# LaserDiode_Driver.net
KiCad netlist of a schematic drawn in Altium Designer
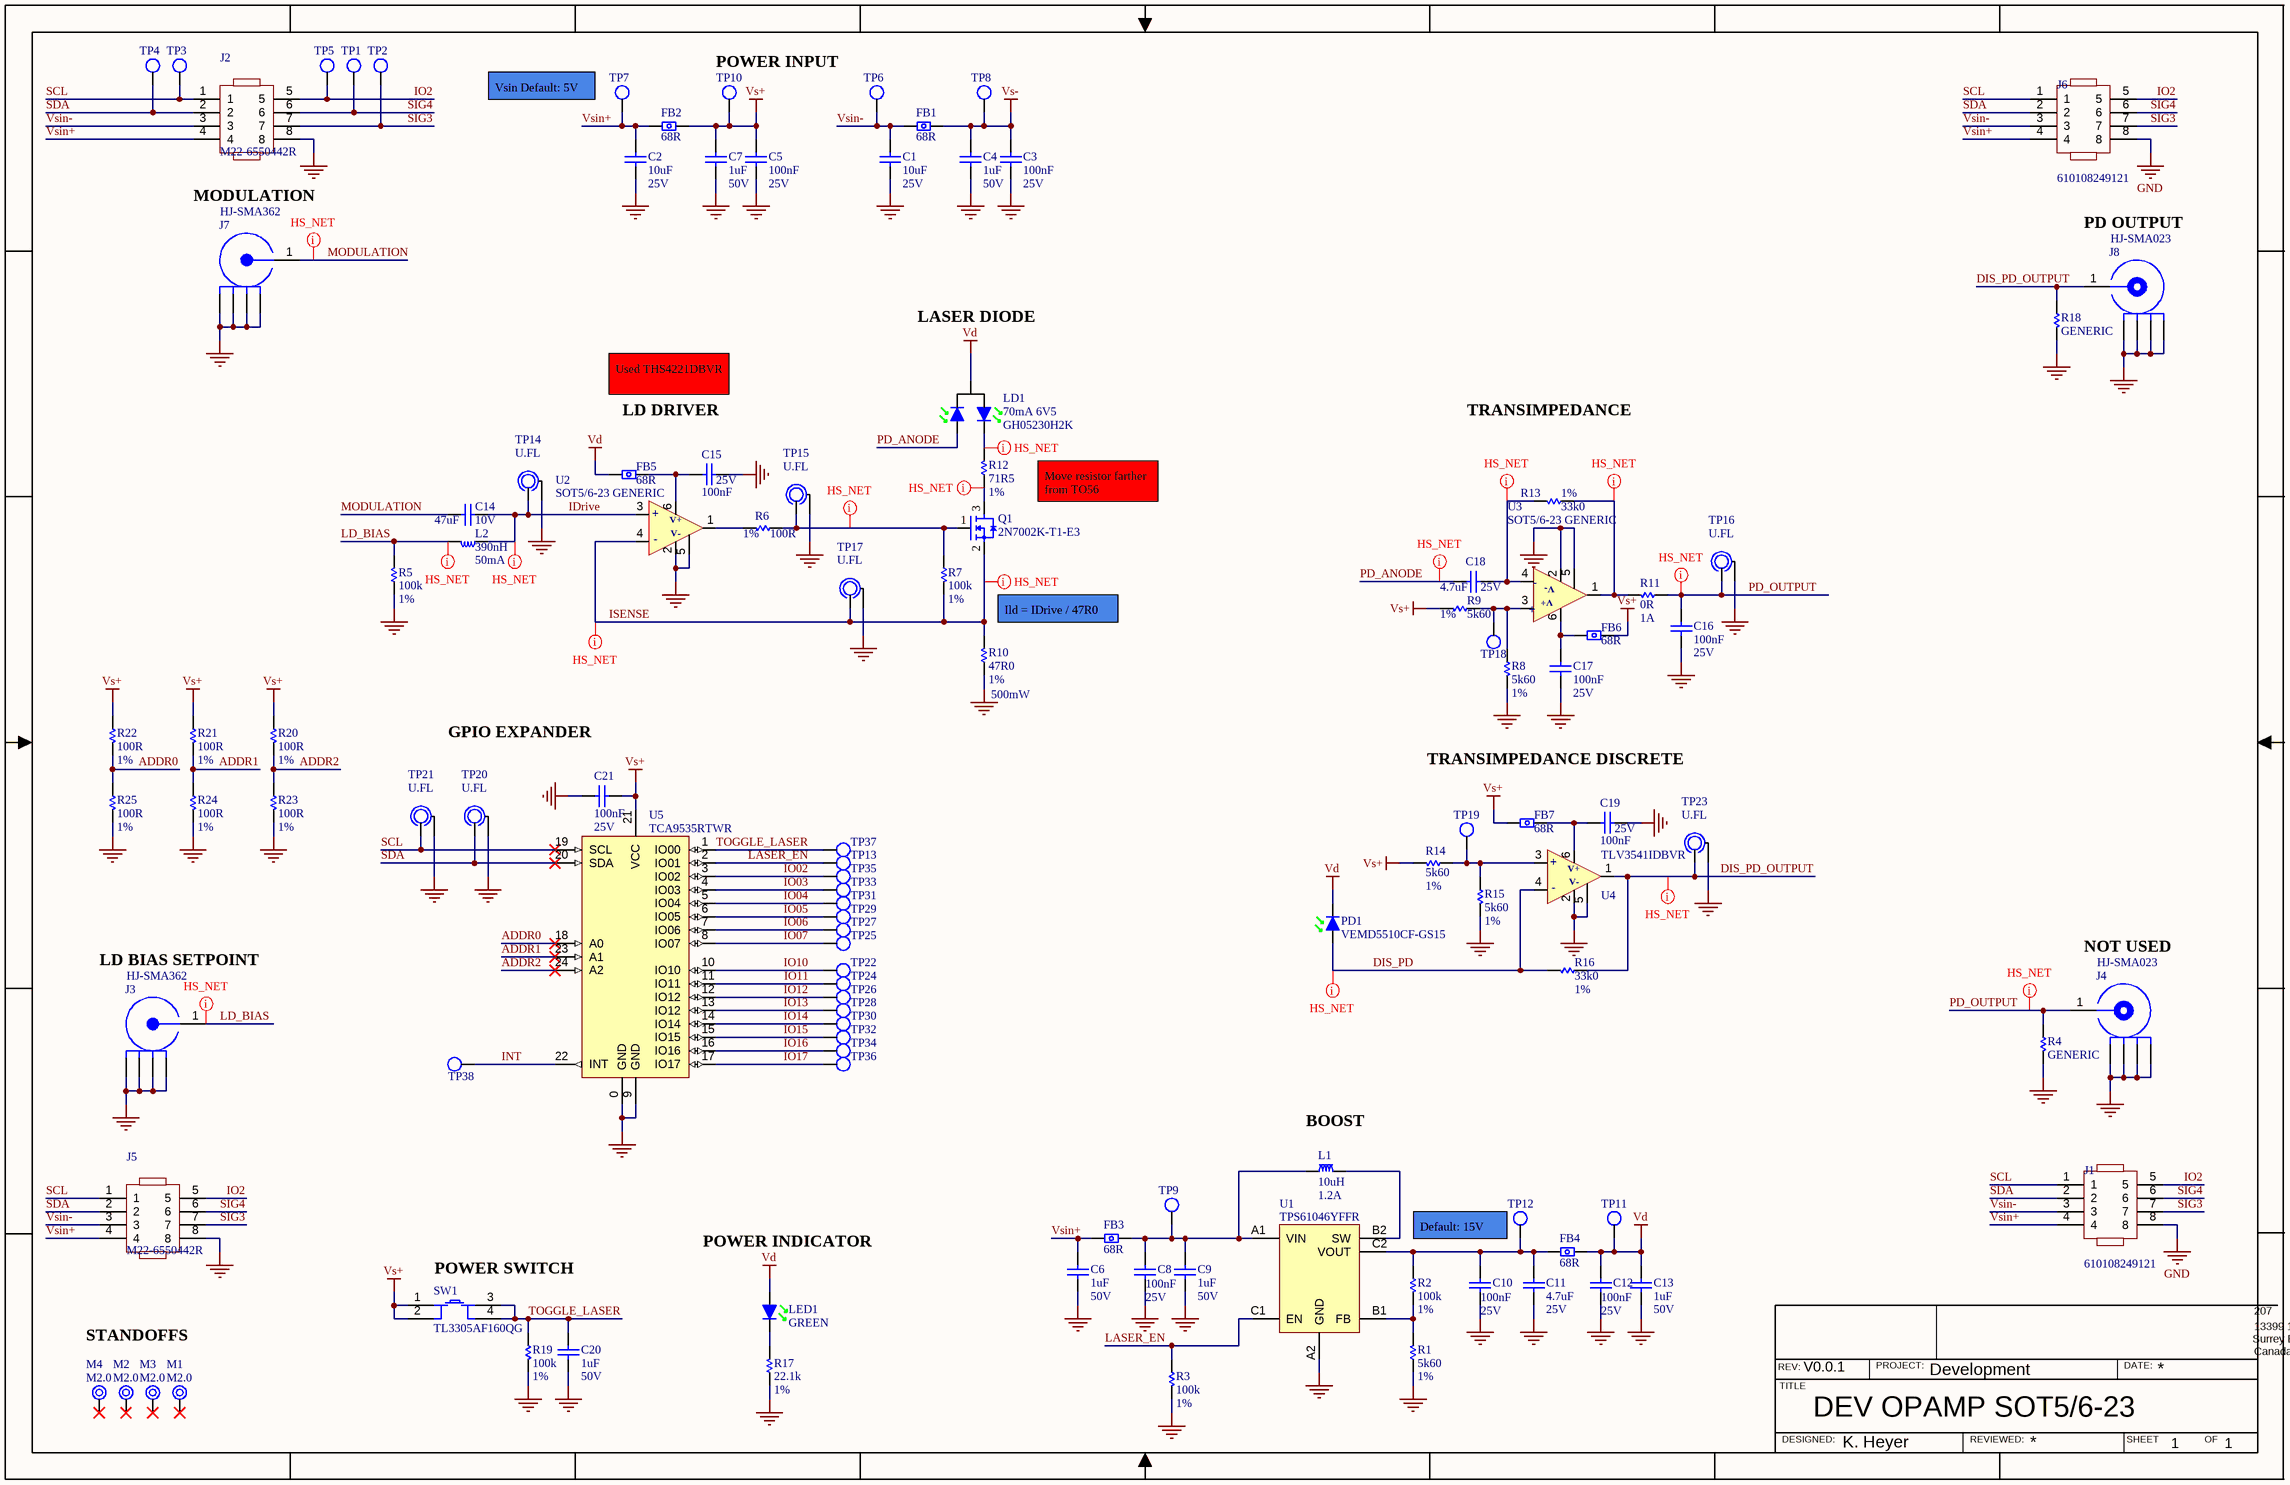
[diagram p0: LaserDiode_Driver.SchDoc]

(export (version "E")
  (design (tool "Eeschema 10.0.6"))
  (components
    (comp (ref "C1")
      (value "10uF")
      (footprint "c0805")
      (description "Cap Ceramic 10uF 25V X5R 10% SMD 0805 85°C Embossed T/R")
      (fields
        (field (name "MANUFACTURER") "Samsung")
        (field (name "MANUFACTURER PART NUMBER") "CL21A106KAYNNNE")
        (field (name "VOLTAGE RATING") "25V")
      )
      (libsource (lib "Symbols") (part "CAP CER 10uF 25V X5R 0805"))
    )
    (comp (ref "C2")
      (value "10uF")
      (footprint "c0805")
      (description "Cap Ceramic 10uF 25V X5R 10% SMD 0805 85°C Embossed T/R")
      (fields
        (field (name "MANUFACTURER") "Samsung")
        (field (name "MANUFACTURER PART NUMBER") "CL21A106KAYNNNE")
        (field (name "VOLTAGE RATING") "25V")
      )
      (libsource (lib "Symbols") (part "CAP CER 10uF 25V X5R 0805"))
    )
    (comp (ref "C3")
      (value "100nF")
      (footprint "C0402")
      (description "Cap Ceramic 0.1uF 25V X5R 10% Pad SMD 0402 85°C T/R / Multi Layer Ceramic Capacitor (MLCC)")
      (fields
        (field (name "MANUFACTURER") "Samsung")
        (field (name "MANUFACTURER PART NUMBER") "CL05A104KA5NNNC")
        (field (name "VOLTAGE RATING") "25V")
      )
      (libsource (lib "Symbols") (part "CAP CER 100nF 25V X5R 0402"))
    )
    (comp (ref "C4")
      (value "1uF")
      (footprint "c0603")
      (description "Multilayer Ceramic Capacitors (High dielectric type), 50V, 1 uF, ± 10 %, 0603, X5R, RoHS")
      (fields
        (field (name "MANUFACTURER") "Taiyo Yuden")
        (field (name "MANUFACTURER PART NUMBER") "UMK107BJ105KA-T")
        (field (name "VOLTAGE RATING") "50V")
      )
      (libsource (lib "Symbols") (part "CAP CER 1uF 50V X5R 0603"))
    )
    (comp (ref "C5")
      (value "100nF")
      (footprint "C0402")
      (description "Cap Ceramic 0.1uF 25V X5R 10% Pad SMD 0402 85°C T/R / Multi Layer Ceramic Capacitor (MLCC)")
      (fields
        (field (name "MANUFACTURER") "Samsung")
        (field (name "MANUFACTURER PART NUMBER") "CL05A104KA5NNNC")
        (field (name "VOLTAGE RATING") "25V")
      )
      (libsource (lib "Symbols") (part "CAP CER 100nF 25V X5R 0402"))
    )
    (comp (ref "C6")
      (value "1uF")
      (footprint "c0603")
      (description "Multilayer Ceramic Capacitors (High dielectric type), 50V, 1 uF, ± 10 %, 0603, X5R, RoHS")
      (fields
        (field (name "MANUFACTURER") "Taiyo Yuden")
        (field (name "MANUFACTURER PART NUMBER") "UMK107BJ105KA-T")
        (field (name "VOLTAGE RATING") "50V")
      )
      (libsource (lib "Symbols") (part "CAP CER 1uF 50V X5R 0603"))
    )
    (comp (ref "C7")
      (value "1uF")
      (footprint "c0603")
      (description "Multilayer Ceramic Capacitors (High dielectric type), 50V, 1 uF, ± 10 %, 0603, X5R, RoHS")
      (fields
        (field (name "MANUFACTURER") "Taiyo Yuden")
        (field (name "MANUFACTURER PART NUMBER") "UMK107BJ105KA-T")
        (field (name "VOLTAGE RATING") "50V")
      )
      (libsource (lib "Symbols") (part "CAP CER 1uF 50V X5R 0603"))
    )
    (comp (ref "C8")
      (value "100nF")
      (footprint "C0402")
      (description "Cap Ceramic 0.1uF 25V X5R 10% Pad SMD 0402 85°C T/R / Multi Layer Ceramic Capacitor (MLCC)")
      (fields
        (field (name "MANUFACTURER") "Samsung")
        (field (name "MANUFACTURER PART NUMBER") "CL05A104KA5NNNC")
        (field (name "VOLTAGE RATING") "25V")
      )
      (libsource (lib "Symbols") (part "CAP CER 100nF 25V X5R 0402"))
    )
    (comp (ref "C9")
      (value "1uF")
      (footprint "c0603")
      (description "Multilayer Ceramic Capacitors (High dielectric type), 50V, 1 uF, ± 10 %, 0603, X5R, RoHS")
      (fields
        (field (name "MANUFACTURER") "Taiyo Yuden")
        (field (name "MANUFACTURER PART NUMBER") "UMK107BJ105KA-T")
        (field (name "VOLTAGE RATING") "50V")
      )
      (libsource (lib "Symbols") (part "CAP CER 1uF 50V X5R 0603"))
    )
    (comp (ref "C10")
      (value "100nF")
      (footprint "C0402")
      (description "Cap Ceramic 0.1uF 25V X5R 10% Pad SMD 0402 85°C T/R / Multi Layer Ceramic Capacitor (MLCC)")
      (fields
        (field (name "MANUFACTURER") "Samsung")
        (field (name "MANUFACTURER PART NUMBER") "CL05A104KA5NNNC")
        (field (name "VOLTAGE RATING") "25V")
      )
      (libsource (lib "Symbols") (part "CAP CER 100nF 25V X5R 0402"))
    )
    (comp (ref "C11")
      (value "4.7uF")
      (footprint "c0805")
      (description "Cap Ceramic 4.7uF 25V X5R 10% SMD 0805 85C Embossed T/R")
      (fields
        (field (name "MANUFACTURER") "Samsung")
        (field (name "MANUFACTURER PART NUMBER") "CL21A475KAQNNNE")
        (field (name "VOLTAGE RATING") "25V")
      )
      (libsource (lib "Symbols") (part "CAP CER 4.7uF 25V X5R 0805"))
    )
    (comp (ref "C12")
      (value "100nF")
      (footprint "C0402")
      (description "Cap Ceramic 0.1uF 25V X5R 10% Pad SMD 0402 85°C T/R / Multi Layer Ceramic Capacitor (MLCC)")
      (fields
        (field (name "MANUFACTURER") "Samsung")
        (field (name "MANUFACTURER PART NUMBER") "CL05A104KA5NNNC")
        (field (name "VOLTAGE RATING") "25V")
      )
      (libsource (lib "Symbols") (part "CAP CER 100nF 25V X5R 0402"))
    )
    (comp (ref "C13")
      (value "1uF")
      (footprint "c0603")
      (description "Multilayer Ceramic Capacitors (High dielectric type), 50V, 1 uF, ± 10 %, 0603, X5R, RoHS")
      (fields
        (field (name "MANUFACTURER") "Taiyo Yuden")
        (field (name "MANUFACTURER PART NUMBER") "UMK107BJ105KA-T")
        (field (name "VOLTAGE RATING") "50V")
      )
      (libsource (lib "Symbols") (part "CAP CER 1uF 50V X5R 0603"))
    )
    (comp (ref "C14")
      (value "47uF")
      (footprint "C1210")
      (description "CAP CER 47UF 10V 20% X7R 1210")
      (fields
        (field (name "MANUFACTURER") "Murata")
        (field (name "MANUFACTURER PART NUMBER") "GRM32ER71A476ME15L")
        (field (name "VOLTAGE RATING") "10V")
      )
      (libsource (lib "Symbols") (part "CAP CER 47uF 10V X7R 1210"))
    )
    (comp (ref "C15")
      (value "100nF")
      (footprint "C0402")
      (description "Cap Ceramic 0.1uF 25V X5R 10% Pad SMD 0402 85°C T/R / Multi Layer Ceramic Capacitor (MLCC)")
      (fields
        (field (name "MANUFACTURER") "Samsung")
        (field (name "MANUFACTURER PART NUMBER") "CL05A104KA5NNNC")
        (field (name "VOLTAGE RATING") "25V")
      )
      (libsource (lib "Symbols") (part "CAP CER 100nF 25V X5R 0402"))
    )
    (comp (ref "C16")
      (value "100nF")
      (footprint "C0402")
      (description "Cap Ceramic 0.1uF 25V X5R 10% Pad SMD 0402 85°C T/R / Multi Layer Ceramic Capacitor (MLCC)")
      (fields
        (field (name "MANUFACTURER") "Samsung")
        (field (name "MANUFACTURER PART NUMBER") "CL05A104KA5NNNC")
        (field (name "VOLTAGE RATING") "25V")
      )
      (libsource (lib "Symbols") (part "CAP CER 100nF 25V X5R 0402"))
    )
    (comp (ref "C17")
      (value "100nF")
      (footprint "C0402")
      (description "Cap Ceramic 0.1uF 25V X5R 10% Pad SMD 0402 85°C T/R / Multi Layer Ceramic Capacitor (MLCC)")
      (fields
        (field (name "MANUFACTURER") "Samsung")
        (field (name "MANUFACTURER PART NUMBER") "CL05A104KA5NNNC")
        (field (name "VOLTAGE RATING") "25V")
      )
      (libsource (lib "Symbols") (part "CAP CER 100nF 25V X5R 0402"))
    )
    (comp (ref "C18")
      (value "4.7uF")
      (footprint "c0805")
      (description "Cap Ceramic 4.7uF 25V X5R 10% SMD 0805 85C Embossed T/R")
      (fields
        (field (name "MANUFACTURER") "Samsung")
        (field (name "MANUFACTURER PART NUMBER") "CL21A475KAQNNNE")
        (field (name "VOLTAGE RATING") "25V")
      )
      (libsource (lib "Symbols") (part "CAP CER 4.7uF 25V X5R 0805"))
    )
    (comp (ref "C19")
      (value "100nF")
      (footprint "C0402")
      (description "Cap Ceramic 0.1uF 25V X5R 10% Pad SMD 0402 85°C T/R / Multi Layer Ceramic Capacitor (MLCC)")
      (fields
        (field (name "MANUFACTURER") "Samsung")
        (field (name "MANUFACTURER PART NUMBER") "CL05A104KA5NNNC")
        (field (name "VOLTAGE RATING") "25V")
      )
      (libsource (lib "Symbols") (part "CAP CER 100nF 25V X5R 0402"))
    )
    (comp (ref "C20")
      (value "1uF")
      (footprint "c0603")
      (description "Multilayer Ceramic Capacitors (High dielectric type), 50V, 1 uF, ± 10 %, 0603, X5R, RoHS")
      (fields
        (field (name "MANUFACTURER") "Taiyo Yuden")
        (field (name "MANUFACTURER PART NUMBER") "UMK107BJ105KA-T")
        (field (name "VOLTAGE RATING") "50V")
      )
      (libsource (lib "Symbols") (part "CAP CER 1uF 50V X5R 0603"))
    )
    (comp (ref "C21")
      (value "100nF")
      (footprint "C0402")
      (description "Cap Ceramic 0.1uF 25V X5R 10% Pad SMD 0402 85°C T/R / Multi Layer Ceramic Capacitor (MLCC)")
      (fields
        (field (name "MANUFACTURER") "Samsung")
        (field (name "MANUFACTURER PART NUMBER") "CL05A104KA5NNNC")
        (field (name "VOLTAGE RATING") "25V")
      )
      (libsource (lib "Symbols") (part "CAP CER 100nF 25V X5R 0402"))
    )
    (comp (ref "FB1")
      (value "68R")
      (footprint "FB0402")
      (description "Ferrite Beads Multi-Layer 68Ohm 25% 100MHz 400mA 310mOhm DCR 0402 T/R")
      (fields
        (field (name "MANUFACTURER") "Taiyo Yuden")
        (field (name "MANUFACTURER PART NUMBER") "BK1005LL680-T")
      )
      (libsource (lib "Symbols") (part "FB 68R 400mA 310mR 0402"))
    )
    (comp (ref "FB2")
      (value "68R")
      (footprint "FB0402")
      (description "Ferrite Beads Multi-Layer 68Ohm 25% 100MHz 400mA 310mOhm DCR 0402 T/R")
      (fields
        (field (name "MANUFACTURER") "Taiyo Yuden")
        (field (name "MANUFACTURER PART NUMBER") "BK1005LL680-T")
      )
      (libsource (lib "Symbols") (part "FB 68R 400mA 310mR 0402"))
    )
    (comp (ref "FB3")
      (value "68R")
      (footprint "FB0402")
      (description "Ferrite Beads Multi-Layer 68Ohm 25% 100MHz 400mA 310mOhm DCR 0402 T/R")
      (fields
        (field (name "MANUFACTURER") "Taiyo Yuden")
        (field (name "MANUFACTURER PART NUMBER") "BK1005LL680-T")
      )
      (libsource (lib "Symbols") (part "FB 68R 400mA 310mR 0402"))
    )
    (comp (ref "FB4")
      (value "68R")
      (footprint "FB0402")
      (description "Ferrite Beads Multi-Layer 68Ohm 25% 100MHz 400mA 310mOhm DCR 0402 T/R")
      (fields
        (field (name "MANUFACTURER") "Taiyo Yuden")
        (field (name "MANUFACTURER PART NUMBER") "BK1005LL680-T")
      )
      (libsource (lib "Symbols") (part "FB 68R 400mA 310mR 0402"))
    )
    (comp (ref "FB5")
      (value "68R")
      (footprint "FB0402")
      (description "Ferrite Beads Multi-Layer 68Ohm 25% 100MHz 400mA 310mOhm DCR 0402 T/R")
      (fields
        (field (name "MANUFACTURER") "Taiyo Yuden")
        (field (name "MANUFACTURER PART NUMBER") "BK1005LL680-T")
      )
      (libsource (lib "Symbols") (part "FB 68R 400mA 310mR 0402"))
    )
    (comp (ref "FB6")
      (value "68R")
      (footprint "FB0402")
      (description "Ferrite Beads Multi-Layer 68Ohm 25% 100MHz 400mA 310mOhm DCR 0402 T/R")
      (fields
        (field (name "MANUFACTURER") "Taiyo Yuden")
        (field (name "MANUFACTURER PART NUMBER") "BK1005LL680-T")
      )
      (libsource (lib "Symbols") (part "FB 68R 400mA 310mR 0402"))
    )
    (comp (ref "FB7")
      (value "68R")
      (footprint "FB0402")
      (description "Ferrite Beads Multi-Layer 68Ohm 25% 100MHz 400mA 310mOhm DCR 0402 T/R")
      (fields
        (field (name "MANUFACTURER") "Taiyo Yuden")
        (field (name "MANUFACTURER PART NUMBER") "BK1005LL680-T")
      )
      (libsource (lib "Symbols") (part "FB 68R 400mA 310mR 0402"))
    )
    (comp (ref "J1")
      (value "610108249121")
      (footprint "CONN HDR 08 MALE RA 2ROW - duplicate")
      (description "SMT Angled Pin Header WR-PHD, Pitch 2.54 mm, Dual Row, 8 pins")
      (fields (field (name "MANUFACTURER") "Wurth Electronics"))
      (libsource (lib "Symbols") (part "CONN HDR 08 MALE RA 2 ROW"))
    )
    (comp (ref "J2")
      (value "M22-6550442R")
      (footprint "CONN HDR 08 FEMALE RA 2ROW")
      (description "Conn Socket Strip RCP 8 POS 2mm Solder RA SMD T/R")
      (fields (field (name "MANUFACTURER") "Harwin"))
      (libsource (lib "Symbols") (part "CONN HDR 08 FEMALE RA 2 ROW"))
    )
    (comp (ref "J3")
      (value "HJ-SMA362")
      (footprint "SMA SMD PIN BRD EDGE")
      (libsource (lib "Symbols") (part "CON SMA PIN SMD BRD EDGE HJ-SMA362"))
    )
    (comp (ref "J4")
      (value "HJ-SMA023")
      (footprint "SMA SMD BORE BRD EDGE")
      (libsource (lib "Symbols") (part "CON SMA BORE SMD BRD EDGE HJ-SMA023"))
    )
    (comp (ref "J5")
      (value "M22-6550442R")
      (footprint "CONN HDR 08 FEMALE RA 2ROW")
      (description "Conn Socket Strip RCP 8 POS 2mm Solder RA SMD T/R")
      (fields (field (name "MANUFACTURER") "Harwin"))
      (libsource (lib "Symbols") (part "CONN HDR 08 FEMALE RA 2 ROW"))
    )
    (comp (ref "J6")
      (value "610108249121")
      (footprint "CONN HDR 08 MALE RA 2ROW - duplicate")
      (description "SMT Angled Pin Header WR-PHD, Pitch 2.54 mm, Dual Row, 8 pins")
      (fields (field (name "MANUFACTURER") "Wurth Electronics"))
      (libsource (lib "Symbols") (part "CONN HDR 08 MALE RA 2 ROW"))
    )
    (comp (ref "J7")
      (value "HJ-SMA362")
      (footprint "SMA SMD PIN BRD EDGE")
      (libsource (lib "Symbols") (part "CON SMA PIN SMD BRD EDGE HJ-SMA362"))
    )
    (comp (ref "J8")
      (value "HJ-SMA023")
      (footprint "SMA SMD BORE BRD EDGE")
      (libsource (lib "Symbols") (part "CON SMA BORE SMD BRD EDGE HJ-SMA023"))
    )
    (comp (ref "L1")
      (value "10uH")
      (footprint "INDP4040X27N")
      (description "Inductor Power Shielded Wirewound 10uH 20% 100KHz Ferrite 1.2A 0.18Ohm DCR 1515 T/R")
      (fields
        (field (name "MANUFACTURER") "Taiyo Yuden")
        (field (name "MANUFACTURER PART NUMBER") "NRS4018T100MDGJ")
        (field (name "CURRENT RATING") "1.2A")
      )
      (libsource (lib "Symbols") (part "IND 10uH 1.2A 180mR 4040 NRS4018T100MDGJ"))
    )
    (comp (ref "L2")
      (value "390nH")
      (footprint "L0402")
      (fields
        (field (name "MANUFACTURER") "TDK")
        (field (name "MANUFACTURER PART NUMBER") "MLG1005SR39JT000")
        (field (name "TOLERANCE") "5%")
        (field (name "CURRENT RATING") "50mA")
      )
      (libsource (lib "Symbols") (part "IND HF 390nH 50mA 8R 0402"))
    )
    (comp (ref "LD1")
      (value "70mA 6V5")
      (footprint "LD TO-56")
      (fields (field (name "MANUFACTURER") "Sharp") (field (name "MANUFACTURER PART NUMBER") "GH05230H2K"))
      (libsource (lib "Symbols") (part "LD TYPE A GREEN 30mW GH05230H2K"))
    )
    (comp (ref "LED1")
      (value "GREEN")
      (footprint "led0402 green")
      (description "LED GREEN CLEAR 0402 SMD")
      (fields
        (field (name "MANUFACTURER") "Kingbright")
        (field (name "MANUFACTURER PART NUMBER") "APHHS1005CGCK")
      )
      (libsource (lib "Symbols") (part "LED GREEN CLEAR 0402"))
    )
    (comp (ref "M1")
      (value "M2.0")
      (footprint "MECH M2.0 UNPLATED")
      (libsource (lib "Symbols") (part "MECH M2.0 UNPLATED"))
    )
    (comp (ref "M2")
      (value "M2.0")
      (footprint "MECH M2.0 UNPLATED")
      (libsource (lib "Symbols") (part "MECH M2.0 UNPLATED"))
    )
    (comp (ref "M3")
      (value "M2.0")
      (footprint "MECH M2.0 UNPLATED")
      (libsource (lib "Symbols") (part "MECH M2.0 UNPLATED"))
    )
    (comp (ref "M4")
      (value "M2.0")
      (footprint "MECH M2.0 UNPLATED")
      (libsource (lib "Symbols") (part "MECH M2.0 UNPLATED"))
    )
    (comp (ref "PD1")
      (value "VEMD5510CF-GS15")
      (footprint "PIN 4x5 4pin")
      (description "Photodiode PIN Chip 540nm 4-Pin SMD T/R")
      (libsource (lib "Symbols") (part "DIODE PHOTO 540nm 20V VEMD5510CF-GS15"))
    )
    (comp (ref "Q1")
      (value "2N7002K-T1-E3")
      (footprint "SOT 23-3")
      (description "Trans MOSFET N-CH 60V 0.3A 3-Pin SOT-23 T/R - Tape and Reel (Alt: 2N7002K-T1-E3)")
      (fields (field (name "MANUFACTURER") "Vishay Siliconix"))
      (libsource (lib "Symbols") (part "TRANS NMOS 60V SOT-23-3 2N7002K-T1-E3"))
    )
    (comp (ref "R1")
      (value "5k60")
      (footprint "R0402")
      (description "Res Thick Film 0402 5.6K Ohm 1% 0.063W(1/16W) ±100ppm/C Epoxy SMD T/R")
      (fields
        (field (name "MANUFACTURER") "Yageo")
        (field (name "MANUFACTURER PART NUMBER") "RC0402FR-075K6L")
        (field (name "TOLERANCE") "1%")
      )
      (libsource (lib "Symbols") (part "RES 5k60 1% 63mW 0402"))
    )
    (comp (ref "R2")
      (value "100k")
      (footprint "r0402")
      (description "Res Thick Film 0402 100K Ohm 1% 0.063W ±100ppm/°C Molded SMD Paper T/R")
      (fields
        (field (name "MANUFACTURER") "Stackpole Electronics")
        (field (name "MANUFACTURER PART NUMBER") "RMCF0402FT100K")
        (field (name "TOLERANCE") "1%")
      )
      (libsource (lib "Symbols") (part "RES 100k 1% 63mW 0402"))
    )
    (comp (ref "R3")
      (value "100k")
      (footprint "r0402")
      (description "Res Thick Film 0402 100K Ohm 1% 0.063W ±100ppm/°C Molded SMD Paper T/R")
      (fields
        (field (name "MANUFACTURER") "Stackpole Electronics")
        (field (name "MANUFACTURER PART NUMBER") "RMCF0402FT100K")
        (field (name "TOLERANCE") "1%")
      )
      (libsource (lib "Symbols") (part "RES 100k 1% 63mW 0402"))
    )
    (comp (ref "R4")
      (value "GENERIC")
      (footprint "R0402")
      (libsource (lib "Symbols") (part "RES GENERIC 0402"))
    )
    (comp (ref "R5")
      (value "100k")
      (footprint "r0402")
      (description "Res Thick Film 0402 100K Ohm 1% 0.063W ±100ppm/°C Molded SMD Paper T/R")
      (fields
        (field (name "MANUFACTURER") "Stackpole Electronics")
        (field (name "MANUFACTURER PART NUMBER") "RMCF0402FT100K")
        (field (name "TOLERANCE") "1%")
      )
      (libsource (lib "Symbols") (part "RES 100k 1% 63mW 0402"))
    )
    (comp (ref "R6")
      (value "100R")
      (footprint "R0402")
      (description "Res General Purpose Thick Film 0402 100 Ohm 1% 1/16W ±100ppm/°C Molded SMD Paper T/R")
      (fields
        (field (name "MANUFACTURER") "Yageo")
        (field (name "MANUFACTURER PART NUMBER") "RC0402FR-07100RL")
        (field (name "TOLERANCE") "1%")
      )
      (libsource (lib "Symbols") (part "RES 100R 63mW 1% 0402"))
    )
    (comp (ref "R7")
      (value "100k")
      (footprint "r0402")
      (description "Res Thick Film 0402 100K Ohm 1% 0.063W ±100ppm/°C Molded SMD Paper T/R")
      (fields
        (field (name "MANUFACTURER") "Stackpole Electronics")
        (field (name "MANUFACTURER PART NUMBER") "RMCF0402FT100K")
        (field (name "TOLERANCE") "1%")
      )
      (libsource (lib "Symbols") (part "RES 100k 1% 63mW 0402"))
    )
    (comp (ref "R8")
      (value "5k60")
      (footprint "R0402")
      (description "Res Thick Film 0402 5.6K Ohm 1% 0.063W(1/16W) ±100ppm/C Epoxy SMD T/R")
      (fields
        (field (name "MANUFACTURER") "Yageo")
        (field (name "MANUFACTURER PART NUMBER") "RC0402FR-075K6L")
        (field (name "TOLERANCE") "1%")
      )
      (libsource (lib "Symbols") (part "RES 5k60 1% 63mW 0402"))
    )
    (comp (ref "R9")
      (value "5k60")
      (footprint "R0402")
      (description "Res Thick Film 0402 5.6K Ohm 1% 0.063W(1/16W) ±100ppm/C Epoxy SMD T/R")
      (fields
        (field (name "MANUFACTURER") "Yageo")
        (field (name "MANUFACTURER PART NUMBER") "RC0402FR-075K6L")
        (field (name "TOLERANCE") "1%")
      )
      (libsource (lib "Symbols") (part "RES 5k60 1% 63mW 0402"))
    )
    (comp (ref "R10")
      (value "47R0")
      (footprint "R0805")
      (description "Res Thick Film 0805 47 Ohm 1% 0.5W(1/2W) ±100ppm/C Pad SMD Automotive T/R")
      (fields (field (name "MAX POWER DISSIPATION") "500mW") (field (name "TOLERANCE") "1%"))
      (libsource (lib "Symbols") (part "RES 47R0 1% 500mW 0805"))
    )
    (comp (ref "R11")
      (value "0R")
      (footprint "R0402")
      (description "GLOVE, POLYAMIDE, L/FREE, PU, SIZE 6 - More Details")
      (fields
        (field (name "MANUFACTURER") "Stackpole Electronics")
        (field (name "MANUFACTURER PART NUMBER") "RMCF0402ZT0R00")
        (field (name "CURRENT RATING") "1A")
      )
      (libsource (lib "Symbols") (part "RES 0R 63mW 0402"))
    )
    (comp (ref "R12")
      (value "71R5")
      (footprint "R0805")
      (description "Res Thick Film 0805 71.5 Ohm 1% 0.25W ±100ppm/°C Molded SMD Punched Carrier T/R")
      (fields (field (name "TOLERANCE") "1%"))
      (libsource (lib "Symbols") (part "RES 71R5 1% 500mW 0402"))
    )
    (comp (ref "R13")
      (value "33k0")
      (footprint "R0603")
      (description "SMD Chip Resistor, 33 kOhm, ± 1%, 100 mW, 0603 [1608 Metric], Thick Film, General Purpose")
      (fields (field (name "TOLERANCE") "1%"))
      (libsource (lib "Symbols") (part "RES 33k0 1% 100mW 0603"))
    )
    (comp (ref "R14")
      (value "5k60")
      (footprint "R0402")
      (description "Res Thick Film 0402 5.6K Ohm 1% 0.063W(1/16W) ±100ppm/C Epoxy SMD T/R")
      (fields
        (field (name "MANUFACTURER") "Yageo")
        (field (name "MANUFACTURER PART NUMBER") "RC0402FR-075K6L")
        (field (name "TOLERANCE") "1%")
      )
      (libsource (lib "Symbols") (part "RES 5k60 1% 63mW 0402"))
    )
    (comp (ref "R15")
      (value "5k60")
      (footprint "R0402")
      (description "Res Thick Film 0402 5.6K Ohm 1% 0.063W(1/16W) ±100ppm/C Epoxy SMD T/R")
      (fields
        (field (name "MANUFACTURER") "Yageo")
        (field (name "MANUFACTURER PART NUMBER") "RC0402FR-075K6L")
        (field (name "TOLERANCE") "1%")
      )
      (libsource (lib "Symbols") (part "RES 5k60 1% 63mW 0402"))
    )
    (comp (ref "R16")
      (value "33k0")
      (footprint "R0603")
      (description "SMD Chip Resistor, 33 kOhm, ± 1%, 100 mW, 0603 [1608 Metric], Thick Film, General Purpose")
      (fields (field (name "TOLERANCE") "1%"))
      (libsource (lib "Symbols") (part "RES 33k0 1% 100mW 0603"))
    )
    (comp (ref "R17")
      (value "22.1k")
      (footprint "R0402")
      (description "Res Thick Film 0402 22.1K Ohm 1% 0.063W(1/16W) ±100ppm/°C Pad SMD T/R")
      (fields
        (field (name "MANUFACTURER") "Yageo")
        (field (name "MANUFACTURER PART NUMBER") "RC0402FR-0722K1L")
        (field (name "TOLERANCE") "1%")
      )
      (libsource (lib "Symbols") (part "RES 22.1k 1% 63mW 0402"))
    )
    (comp (ref "R18")
      (value "GENERIC")
      (footprint "R0402")
      (libsource (lib "Symbols") (part "RES GENERIC 0402"))
    )
    (comp (ref "R19")
      (value "100k")
      (footprint "r0402")
      (description "Res Thick Film 0402 100K Ohm 1% 0.063W ±100ppm/°C Molded SMD Paper T/R")
      (fields
        (field (name "MANUFACTURER") "Stackpole Electronics")
        (field (name "MANUFACTURER PART NUMBER") "RMCF0402FT100K")
        (field (name "TOLERANCE") "1%")
      )
      (libsource (lib "Symbols") (part "RES 100k 1% 63mW 0402"))
    )
    (comp (ref "R20")
      (value "100R")
      (footprint "R0402")
      (description "Res General Purpose Thick Film 0402 100 Ohm 1% 1/16W ±100ppm/°C Molded SMD Paper T/R")
      (fields
        (field (name "MANUFACTURER") "Yageo")
        (field (name "MANUFACTURER PART NUMBER") "RC0402FR-07100RL")
        (field (name "TOLERANCE") "1%")
      )
      (libsource (lib "Symbols") (part "RES 100R 63mW 1% 0402"))
    )
    (comp (ref "R21")
      (value "100R")
      (footprint "R0402")
      (description "Res General Purpose Thick Film 0402 100 Ohm 1% 1/16W ±100ppm/°C Molded SMD Paper T/R")
      (fields
        (field (name "MANUFACTURER") "Yageo")
        (field (name "MANUFACTURER PART NUMBER") "RC0402FR-07100RL")
        (field (name "TOLERANCE") "1%")
      )
      (libsource (lib "Symbols") (part "RES 100R 63mW 1% 0402"))
    )
    (comp (ref "R22")
      (value "100R")
      (footprint "R0402")
      (description "Res General Purpose Thick Film 0402 100 Ohm 1% 1/16W ±100ppm/°C Molded SMD Paper T/R")
      (fields
        (field (name "MANUFACTURER") "Yageo")
        (field (name "MANUFACTURER PART NUMBER") "RC0402FR-07100RL")
        (field (name "TOLERANCE") "1%")
      )
      (libsource (lib "Symbols") (part "RES 100R 63mW 1% 0402"))
    )
    (comp (ref "R23")
      (value "100R")
      (footprint "R0402")
      (description "Res General Purpose Thick Film 0402 100 Ohm 1% 1/16W ±100ppm/°C Molded SMD Paper T/R")
      (fields
        (field (name "MANUFACTURER") "Yageo")
        (field (name "MANUFACTURER PART NUMBER") "RC0402FR-07100RL")
        (field (name "TOLERANCE") "1%")
      )
      (libsource (lib "Symbols") (part "RES 100R 63mW 1% 0402"))
    )
    (comp (ref "R24")
      (value "100R")
      (footprint "R0402")
      (description "Res General Purpose Thick Film 0402 100 Ohm 1% 1/16W ±100ppm/°C Molded SMD Paper T/R")
      (fields
        (field (name "MANUFACTURER") "Yageo")
        (field (name "MANUFACTURER PART NUMBER") "RC0402FR-07100RL")
        (field (name "TOLERANCE") "1%")
      )
      (libsource (lib "Symbols") (part "RES 100R 63mW 1% 0402"))
    )
    (comp (ref "R25")
      (value "100R")
      (footprint "R0402")
      (description "Res General Purpose Thick Film 0402 100 Ohm 1% 1/16W ±100ppm/°C Molded SMD Paper T/R")
      (fields
        (field (name "MANUFACTURER") "Yageo")
        (field (name "MANUFACTURER PART NUMBER") "RC0402FR-07100RL")
        (field (name "TOLERANCE") "1%")
      )
      (libsource (lib "Symbols") (part "RES 100R 63mW 1% 0402"))
    )
    (comp (ref "SW1")
      (value "TL3305AF160QG")
      (footprint "MECH PB TL3305A")
      (description "TL3305A Series SPST 12 V 4.5 x 4.5 mm 160 gf Top Actuated SMT Tactile Switch")
      (fields (field (name "MANUFACTURER") "E-Switch"))
      (libsource (lib "Symbols") (part "MECH PB SPST TL3305AF160QG"))
    )
    (comp (ref "TP1")
      (value "1mm")
      (footprint "TESTPOINT_SMT")
      (description "SMT testpoint")
      (libsource (lib "Symbols") (part "TP 1mm"))
    )
    (comp (ref "TP2")
      (value "1mm")
      (footprint "TESTPOINT_SMT")
      (description "SMT testpoint")
      (libsource (lib "Symbols") (part "TP 1mm"))
    )
    (comp (ref "TP3")
      (value "1mm")
      (footprint "TESTPOINT_SMT")
      (description "SMT testpoint")
      (libsource (lib "Symbols") (part "TP 1mm"))
    )
    (comp (ref "TP4")
      (value "1mm")
      (footprint "TESTPOINT_SMT")
      (description "SMT testpoint")
      (libsource (lib "Symbols") (part "TP 1mm"))
    )
    (comp (ref "TP5")
      (value "1mm")
      (footprint "TESTPOINT_SMT")
      (description "SMT testpoint")
      (libsource (lib "Symbols") (part "TP 1mm"))
    )
    (comp (ref "TP6")
      (value "1mm")
      (footprint "TESTPOINT_SMT")
      (description "SMT testpoint")
      (libsource (lib "Symbols") (part "TP 1mm"))
    )
    (comp (ref "TP7")
      (value "1mm")
      (footprint "TESTPOINT_SMT")
      (description "SMT testpoint")
      (libsource (lib "Symbols") (part "TP 1mm"))
    )
    (comp (ref "TP8")
      (value "1mm")
      (footprint "TESTPOINT_SMT")
      (description "SMT testpoint")
      (libsource (lib "Symbols") (part "TP 1mm"))
    )
    (comp (ref "TP9")
      (value "1mm")
      (footprint "TESTPOINT_SMT")
      (description "SMT testpoint")
      (libsource (lib "Symbols") (part "TP 1mm"))
    )
    (comp (ref "TP10")
      (value "1mm")
      (footprint "TESTPOINT_SMT")
      (description "SMT testpoint")
      (libsource (lib "Symbols") (part "TP 1mm"))
    )
    (comp (ref "TP11")
      (value "1mm")
      (footprint "TESTPOINT_SMT")
      (description "SMT testpoint")
      (libsource (lib "Symbols") (part "TP 1mm"))
    )
    (comp (ref "TP12")
      (value "1mm")
      (footprint "TESTPOINT_SMT")
      (description "SMT testpoint")
      (libsource (lib "Symbols") (part "TP 1mm"))
    )
    (comp (ref "TP13")
      (value "1mm")
      (footprint "TESTPOINT_SMT")
      (description "SMT testpoint")
      (libsource (lib "Symbols") (part "TP 1mm"))
    )
    (comp (ref "TP14")
      (value "U.FL")
      (footprint "U.FL")
      (description "CONN U.FL RCPT STR 50 OHM SMD")
      (fields
        (field (name "MANUFACTURER") "Hirose")
        (field (name "MANUFACTURER PART NUMBER") "U.FL-R-SMT-1(80)")
      )
      (libsource (lib "Symbols") (part "TP U.FL"))
    )
    (comp (ref "TP15")
      (value "U.FL")
      (footprint "U.FL")
      (description "CONN U.FL RCPT STR 50 OHM SMD")
      (fields
        (field (name "MANUFACTURER") "Hirose")
        (field (name "MANUFACTURER PART NUMBER") "U.FL-R-SMT-1(80)")
      )
      (libsource (lib "Symbols") (part "TP U.FL"))
    )
    (comp (ref "TP16")
      (value "U.FL")
      (footprint "U.FL")
      (description "CONN U.FL RCPT STR 50 OHM SMD")
      (fields
        (field (name "MANUFACTURER") "Hirose")
        (field (name "MANUFACTURER PART NUMBER") "U.FL-R-SMT-1(80)")
      )
      (libsource (lib "Symbols") (part "TP U.FL"))
    )
    (comp (ref "TP17")
      (value "U.FL")
      (footprint "U.FL")
      (description "CONN U.FL RCPT STR 50 OHM SMD")
      (fields
        (field (name "MANUFACTURER") "Hirose")
        (field (name "MANUFACTURER PART NUMBER") "U.FL-R-SMT-1(80)")
      )
      (libsource (lib "Symbols") (part "TP U.FL"))
    )
    (comp (ref "TP18")
      (value "1mm")
      (footprint "TESTPOINT_SMT")
      (description "SMT testpoint")
      (libsource (lib "Symbols") (part "TP 1mm"))
    )
    (comp (ref "TP19")
      (value "1mm")
      (footprint "TESTPOINT_SMT")
      (description "SMT testpoint")
      (libsource (lib "Symbols") (part "TP 1mm"))
    )
    (comp (ref "TP20")
      (value "U.FL")
      (footprint "U.FL")
      (description "CONN U.FL RCPT STR 50 OHM SMD")
      (fields
        (field (name "MANUFACTURER") "Hirose")
        (field (name "MANUFACTURER PART NUMBER") "U.FL-R-SMT-1(80)")
      )
      (libsource (lib "Symbols") (part "TP U.FL"))
    )
    (comp (ref "TP21")
      (value "U.FL")
      (footprint "U.FL")
      (description "CONN U.FL RCPT STR 50 OHM SMD")
      (fields
        (field (name "MANUFACTURER") "Hirose")
        (field (name "MANUFACTURER PART NUMBER") "U.FL-R-SMT-1(80)")
      )
      (libsource (lib "Symbols") (part "TP U.FL"))
    )
    (comp (ref "TP22")
      (value "1mm")
      (footprint "TESTPOINT_SMT")
      (description "SMT testpoint")
      (libsource (lib "Symbols") (part "TP 1mm"))
    )
    (comp (ref "TP23")
      (value "U.FL")
      (footprint "U.FL")
      (description "CONN U.FL RCPT STR 50 OHM SMD")
      (fields
        (field (name "MANUFACTURER") "Hirose")
        (field (name "MANUFACTURER PART NUMBER") "U.FL-R-SMT-1(80)")
      )
      (libsource (lib "Symbols") (part "TP U.FL"))
    )
    (comp (ref "TP24")
      (value "1mm")
      (footprint "TESTPOINT_SMT")
      (description "SMT testpoint")
      (libsource (lib "Symbols") (part "TP 1mm"))
    )
    (comp (ref "TP25")
      (value "1mm")
      (footprint "TESTPOINT_SMT")
      (description "SMT testpoint")
      (libsource (lib "Symbols") (part "TP 1mm"))
    )
    (comp (ref "TP26")
      (value "1mm")
      (footprint "TESTPOINT_SMT")
      (description "SMT testpoint")
      (libsource (lib "Symbols") (part "TP 1mm"))
    )
    (comp (ref "TP27")
      (value "1mm")
      (footprint "TESTPOINT_SMT")
      (description "SMT testpoint")
      (libsource (lib "Symbols") (part "TP 1mm"))
    )
    (comp (ref "TP28")
      (value "1mm")
      (footprint "TESTPOINT_SMT")
      (description "SMT testpoint")
      (libsource (lib "Symbols") (part "TP 1mm"))
    )
    (comp (ref "TP29")
      (value "1mm")
      (footprint "TESTPOINT_SMT")
      (description "SMT testpoint")
      (libsource (lib "Symbols") (part "TP 1mm"))
    )
    (comp (ref "TP30")
      (value "1mm")
      (footprint "TESTPOINT_SMT")
      (description "SMT testpoint")
      (libsource (lib "Symbols") (part "TP 1mm"))
    )
    (comp (ref "TP31")
      (value "1mm")
      (footprint "TESTPOINT_SMT")
      (description "SMT testpoint")
      (libsource (lib "Symbols") (part "TP 1mm"))
    )
    (comp (ref "TP32")
      (value "1mm")
      (footprint "TESTPOINT_SMT")
      (description "SMT testpoint")
      (libsource (lib "Symbols") (part "TP 1mm"))
    )
    (comp (ref "TP33")
      (value "1mm")
      (footprint "TESTPOINT_SMT")
      (description "SMT testpoint")
      (libsource (lib "Symbols") (part "TP 1mm"))
    )
    (comp (ref "TP34")
      (value "1mm")
      (footprint "TESTPOINT_SMT")
      (description "SMT testpoint")
      (libsource (lib "Symbols") (part "TP 1mm"))
    )
    (comp (ref "TP35")
      (value "1mm")
      (footprint "TESTPOINT_SMT")
      (description "SMT testpoint")
      (libsource (lib "Symbols") (part "TP 1mm"))
    )
    (comp (ref "TP36")
      (value "1mm")
      (footprint "TESTPOINT_SMT")
      (description "SMT testpoint")
      (libsource (lib "Symbols") (part "TP 1mm"))
    )
    (comp (ref "TP37")
      (value "1mm")
      (footprint "TESTPOINT_SMT")
      (description "SMT testpoint")
      (libsource (lib "Symbols") (part "TP 1mm"))
    )
    (comp (ref "TP38")
      (value "1mm")
      (footprint "TESTPOINT_SMT")
      (description "SMT testpoint")
      (libsource (lib "Symbols") (part "TP 1mm"))
    )
    (comp (ref "U1")
      (value "TPS61046YFFR")
      (footprint "BGA 2x3 0.8x1.2mm TI-YFF0006")
      (description "28-V Output Voltage Boost Converter in WCSP Package 6-DSBGA -40 to 125")
      (fields (field (name "MANUFACTURER") "Texas Instruments"))
      (libsource (lib "Symbols") (part "IC REG BOOST 28V 1A2 TPS61046YFFR"))
    )
    (comp (ref "U2")
      (value "SOT5/6-23 GENERIC")
      (footprint "SOT23-5/6_Modified")
      (libsource (lib "Symbols") (part "IC OPAMP SOT5/6-23 GENERIC"))
    )
    (comp (ref "U3")
      (value "SOT5/6-23 GENERIC")
      (footprint "SOT23-5/6_Modified")
      (libsource (lib "Symbols") (part "IC OPAMP SOT5/6-23 GENERIC"))
    )
    (comp (ref "U4")
      (value "TLV3541IDBVR")
      (footprint "SOT23-5/6_Modified")
      (libsource (lib "Symbols") (part "IC OPAMP SOT5/6-23 GENERIC"))
    )
    (comp (ref "U5")
      (value "TCA9535RTWR")
      (footprint "QFN50P400X400X80_HS-25N")
      (description "IC I/O EXPANDER I2C 16B 24WQFN / I2C/SMBus Interface 100kHz/400kHz 5.5V 24-Pin WQFN EP T/R")
      (libsource (lib "Symbols") (part "IC GPIO EXPANDER 16B I2C TCA9535RTWR"))
    )
  )
  (nets
    (net (code "1") (name "/ADDR0") (class "Default")
      (node (ref "R22") (pin "2") (pinfunction "2_2") (pintype "passive"))
      (node (ref "R25") (pin "1") (pinfunction "1_1") (pintype "passive"))
      (node (ref "U5") (pin "18") (pinfunction "A0_18") (pintype "input"))
    )
    (net (code "2") (name "/ADDR1") (class "Default")
      (node (ref "R21") (pin "2") (pinfunction "2_2") (pintype "passive"))
      (node (ref "R24") (pin "1") (pinfunction "1_1") (pintype "passive"))
      (node (ref "U5") (pin "23") (pinfunction "A1_23") (pintype "input"))
    )
    (net (code "3") (name "/ADDR2") (class "Default")
      (node (ref "R20") (pin "2") (pinfunction "2_2") (pintype "passive"))
      (node (ref "R23") (pin "1") (pinfunction "1_1") (pintype "passive"))
      (node (ref "U5") (pin "24") (pinfunction "A2_24") (pintype "input"))
    )
    (net (code "4") (name "/DIS_PD") (class "Default")
      (node (ref "PD1") (pin "2") (pinfunction "AN_2") (pintype "passive"))
      (node (ref "R16") (pin "2") (pinfunction "2_2") (pintype "passive"))
      (node (ref "U4") (pin "4") (pinfunction "-_4") (pintype "passive"))
    )
    (net (code "5") (name "/DIS_PD_OUTPUT") (class "Default")
      (node (ref "J8") (pin "1") (pinfunction "1_1") (pintype "passive"))
      (node (ref "R16") (pin "1") (pinfunction "1_1") (pintype "passive"))
      (node (ref "R18") (pin "1") (pinfunction "1_1") (pintype "passive"))
      (node (ref "TP23") (pin "1") (pinfunction "1_1") (pintype "passive"))
      (node (ref "U4") (pin "1") (pinfunction "1_1") (pintype "passive"))
    )
    (net (code "6") (name "/IDrive") (class "Default")
      (node (ref "C14") (pin "1") (pinfunction "1_1") (pintype "passive"))
      (node (ref "L2") (pin "2") (pinfunction "2_2") (pintype "passive"))
      (node (ref "TP14") (pin "1") (pinfunction "1_1") (pintype "passive"))
      (node (ref "U2") (pin "3") (pinfunction "+_3") (pintype "passive"))
    )
    (net (code "7") (name "/INT") (class "Default")
      (node (ref "TP38") (pin "1") (pinfunction "1_1") (pintype "passive"))
      (node (ref "U5") (pin "22") (pinfunction "INT_22") (pintype "output"))
    )
    (net (code "8") (name "/IO2") (class "Default")
      (node (ref "J1") (pin "5") (pinfunction "5_5") (pintype "passive"))
      (node (ref "J2") (pin "5") (pinfunction "5_5") (pintype "passive"))
      (node (ref "J5") (pin "5") (pinfunction "5_5") (pintype "passive"))
      (node (ref "J6") (pin "5") (pinfunction "5_5") (pintype "passive"))
      (node (ref "TP5") (pin "1") (pinfunction "1_1") (pintype "passive"))
    )
    (net (code "9") (name "/IO02") (class "Default")
      (node (ref "TP35") (pin "1") (pinfunction "1_1") (pintype "passive"))
      (node (ref "U5") (pin "3") (pinfunction "IO02_3") (pintype "bidirectional"))
    )
    (net (code "10") (name "/IO03") (class "Default")
      (node (ref "TP33") (pin "1") (pinfunction "1_1") (pintype "passive"))
      (node (ref "U5") (pin "4") (pinfunction "IO03_4") (pintype "bidirectional"))
    )
    (net (code "11") (name "/IO04") (class "Default")
      (node (ref "TP31") (pin "1") (pinfunction "1_1") (pintype "passive"))
      (node (ref "U5") (pin "5") (pinfunction "IO04_5") (pintype "bidirectional"))
    )
    (net (code "12") (name "/IO05") (class "Default")
      (node (ref "TP29") (pin "1") (pinfunction "1_1") (pintype "passive"))
      (node (ref "U5") (pin "6") (pinfunction "IO05_6") (pintype "bidirectional"))
    )
    (net (code "13") (name "/IO06") (class "Default")
      (node (ref "TP27") (pin "1") (pinfunction "1_1") (pintype "passive"))
      (node (ref "U5") (pin "7") (pinfunction "IO06_7") (pintype "bidirectional"))
    )
    (net (code "14") (name "/IO07") (class "Default")
      (node (ref "TP25") (pin "1") (pinfunction "1_1") (pintype "passive"))
      (node (ref "U5") (pin "8") (pinfunction "IO07_8") (pintype "bidirectional"))
    )
    (net (code "15") (name "/IO10") (class "Default")
      (node (ref "TP22") (pin "1") (pinfunction "1_1") (pintype "passive"))
      (node (ref "U5") (pin "10") (pinfunction "IO10_10") (pintype "bidirectional"))
    )
    (net (code "16") (name "/IO11") (class "Default")
      (node (ref "TP24") (pin "1") (pinfunction "1_1") (pintype "passive"))
      (node (ref "U5") (pin "11") (pinfunction "IO11_11") (pintype "bidirectional"))
    )
    (net (code "17") (name "/IO12") (class "Default")
      (node (ref "TP26") (pin "1") (pinfunction "1_1") (pintype "passive"))
      (node (ref "U5") (pin "12") (pinfunction "IO12_12") (pintype "bidirectional"))
    )
    (net (code "18") (name "/IO13") (class "Default")
      (node (ref "TP28") (pin "1") (pinfunction "1_1") (pintype "passive"))
      (node (ref "U5") (pin "13") (pinfunction "IO12_13") (pintype "bidirectional"))
    )
    (net (code "19") (name "/IO14") (class "Default")
      (node (ref "TP30") (pin "1") (pinfunction "1_1") (pintype "passive"))
      (node (ref "U5") (pin "14") (pinfunction "IO14_14") (pintype "bidirectional"))
    )
    (net (code "20") (name "/IO15") (class "Default")
      (node (ref "TP32") (pin "1") (pinfunction "1_1") (pintype "passive"))
      (node (ref "U5") (pin "15") (pinfunction "IO15_15") (pintype "bidirectional"))
    )
    (net (code "21") (name "/IO16") (class "Default")
      (node (ref "TP34") (pin "1") (pinfunction "1_1") (pintype "passive"))
      (node (ref "U5") (pin "16") (pinfunction "IO16_16") (pintype "bidirectional"))
    )
    (net (code "22") (name "/IO17") (class "Default")
      (node (ref "TP36") (pin "1") (pinfunction "1_1") (pintype "passive"))
      (node (ref "U5") (pin "17") (pinfunction "IO17_17") (pintype "bidirectional"))
    )
    (net (code "23") (name "/ISENSE") (class "Default")
      (node (ref "Q1") (pin "2") (pinfunction "S_2") (pintype "passive"))
      (node (ref "R10") (pin "2") (pinfunction "2_2") (pintype "passive"))
      (node (ref "R7") (pin "2") (pinfunction "2_2") (pintype "passive"))
      (node (ref "TP17") (pin "1") (pinfunction "1_1") (pintype "passive"))
      (node (ref "U2") (pin "4") (pinfunction "-_4") (pintype "passive"))
    )
    (net (code "24") (name "/LASER_EN") (class "Default")
      (node (ref "R3") (pin "1") (pinfunction "1_1") (pintype "passive"))
      (node (ref "TP13") (pin "1") (pinfunction "1_1") (pintype "passive"))
      (node (ref "U1") (pin "C1") (pinfunction "EN_C1") (pintype "passive"))
      (node (ref "U5") (pin "2") (pinfunction "IO01_2") (pintype "bidirectional"))
    )
    (net (code "25") (name "/LD_BIAS") (class "Default")
      (node (ref "J3") (pin "1") (pinfunction "1_1") (pintype "passive"))
      (node (ref "L2") (pin "1") (pinfunction "1_1") (pintype "passive"))
      (node (ref "R5") (pin "2") (pinfunction "2_2") (pintype "passive"))
    )
    (net (code "26") (name "/MODULATION") (class "Default")
      (node (ref "C14") (pin "2") (pinfunction "2_2") (pintype "passive"))
      (node (ref "J7") (pin "1") (pinfunction "1_1") (pintype "passive"))
    )
    (net (code "27") (name "/PD_ANODE") (class "Default")
      (node (ref "C18") (pin "2") (pinfunction "2_2") (pintype "passive"))
      (node (ref "LD1") (pin "3") (pinfunction "PD_3") (pintype "passive"))
    )
    (net (code "28") (name "/PD_OUTPUT") (class "Default")
      (node (ref "C16") (pin "1") (pinfunction "1_1") (pintype "passive"))
      (node (ref "J4") (pin "1") (pinfunction "1_1") (pintype "passive"))
      (node (ref "R11") (pin "1") (pinfunction "1_1") (pintype "passive"))
      (node (ref "R4") (pin "1") (pinfunction "1_1") (pintype "passive"))
      (node (ref "TP16") (pin "1") (pinfunction "1_1") (pintype "passive"))
    )
    (net (code "29") (name "/SCL") (class "Default")
      (node (ref "J1") (pin "1") (pinfunction "1_1") (pintype "passive"))
      (node (ref "J2") (pin "1") (pinfunction "1_1") (pintype "passive"))
      (node (ref "J5") (pin "1") (pinfunction "1_1") (pintype "passive"))
      (node (ref "J6") (pin "1") (pinfunction "1_1") (pintype "passive"))
      (node (ref "TP21") (pin "1") (pinfunction "1_1") (pintype "passive"))
      (node (ref "TP3") (pin "1") (pinfunction "1_1") (pintype "passive"))
      (node (ref "U5") (pin "19") (pinfunction "SCL_19") (pintype "input"))
    )
    (net (code "30") (name "/SDA") (class "Default")
      (node (ref "J1") (pin "2") (pinfunction "2_2") (pintype "passive"))
      (node (ref "J2") (pin "2") (pinfunction "2_2") (pintype "passive"))
      (node (ref "J5") (pin "2") (pinfunction "2_2") (pintype "passive"))
      (node (ref "J6") (pin "2") (pinfunction "2_2") (pintype "passive"))
      (node (ref "TP20") (pin "1") (pinfunction "1_1") (pintype "passive"))
      (node (ref "TP4") (pin "1") (pinfunction "1_1") (pintype "passive"))
      (node (ref "U5") (pin "20") (pinfunction "SDA_20") (pintype "input"))
    )
    (net (code "31") (name "/SIG3") (class "Default")
      (node (ref "J1") (pin "7") (pinfunction "7_7") (pintype "passive"))
      (node (ref "J2") (pin "7") (pinfunction "7_7") (pintype "passive"))
      (node (ref "J5") (pin "7") (pinfunction "7_7") (pintype "passive"))
      (node (ref "J6") (pin "7") (pinfunction "7_7") (pintype "passive"))
      (node (ref "TP2") (pin "1") (pinfunction "1_1") (pintype "passive"))
    )
    (net (code "32") (name "/SIG4") (class "Default")
      (node (ref "J1") (pin "6") (pinfunction "6_6") (pintype "passive"))
      (node (ref "J2") (pin "6") (pinfunction "6_6") (pintype "passive"))
      (node (ref "J5") (pin "6") (pinfunction "6_6") (pintype "passive"))
      (node (ref "J6") (pin "6") (pinfunction "6_6") (pintype "passive"))
      (node (ref "TP1") (pin "1") (pinfunction "1_1") (pintype "passive"))
    )
    (net (code "33") (name "/TOGGLE_LASER") (class "Default")
      (node (ref "C20") (pin "2") (pinfunction "2_2") (pintype "passive"))
      (node (ref "R19") (pin "1") (pinfunction "1_1") (pintype "passive"))
      (node (ref "SW1") (pin "3") (pinfunction "3_3") (pintype "passive"))
      (node (ref "SW1") (pin "4") (pinfunction "4_4") (pintype "passive"))
      (node (ref "TP37") (pin "1") (pinfunction "1_1") (pintype "passive"))
      (node (ref "U5") (pin "1") (pinfunction "IO00_1") (pintype "bidirectional"))
    )
    (net (code "34") (name "/Vsin+") (class "Default")
      (node (ref "C2") (pin "2") (pinfunction "2_2") (pintype "passive"))
      (node (ref "C6") (pin "2") (pinfunction "2_2") (pintype "passive"))
      (node (ref "FB2") (pin "2") (pintype "passive"))
      (node (ref "FB3") (pin "1") (pintype "passive"))
      (node (ref "J1") (pin "4") (pinfunction "4_4") (pintype "passive"))
      (node (ref "J2") (pin "4") (pinfunction "4_4") (pintype "passive"))
      (node (ref "J5") (pin "4") (pinfunction "4_4") (pintype "passive"))
      (node (ref "J6") (pin "4") (pinfunction "4_4") (pintype "passive"))
      (node (ref "TP7") (pin "1") (pinfunction "1_1") (pintype "passive"))
    )
    (net (code "35") (name "/Vsin-") (class "Default")
      (node (ref "C1") (pin "2") (pinfunction "2_2") (pintype "passive"))
      (node (ref "FB1") (pin "2") (pintype "passive"))
      (node (ref "J1") (pin "3") (pinfunction "3_3") (pintype "passive"))
      (node (ref "J2") (pin "3") (pinfunction "3_3") (pintype "passive"))
      (node (ref "J5") (pin "3") (pinfunction "3_3") (pintype "passive"))
      (node (ref "J6") (pin "3") (pinfunction "3_3") (pintype "passive"))
      (node (ref "TP6") (pin "1") (pinfunction "1_1") (pintype "passive"))
    )
    (net (code "36") (name "GND") (class "Default")
      (node (ref "C1") (pin "1") (pinfunction "1_1") (pintype "passive"))
      (node (ref "C10") (pin "1") (pinfunction "1_1") (pintype "passive"))
      (node (ref "C11") (pin "1") (pinfunction "1_1") (pintype "passive"))
      (node (ref "C12") (pin "1") (pinfunction "1_1") (pintype "passive"))
      (node (ref "C13") (pin "1") (pinfunction "1_1") (pintype "passive"))
      (node (ref "C15") (pin "2") (pinfunction "2_2") (pintype "passive"))
      (node (ref "C16") (pin "2") (pinfunction "2_2") (pintype "passive"))
      (node (ref "C17") (pin "2") (pinfunction "2_2") (pintype "passive"))
      (node (ref "C19") (pin "2") (pinfunction "2_2") (pintype "passive"))
      (node (ref "C2") (pin "1") (pinfunction "1_1") (pintype "passive"))
      (node (ref "C20") (pin "1") (pinfunction "1_1") (pintype "passive"))
      (node (ref "C21") (pin "2") (pinfunction "2_2") (pintype "passive"))
      (node (ref "C3") (pin "1") (pinfunction "1_1") (pintype "passive"))
      (node (ref "C4") (pin "1") (pinfunction "1_1") (pintype "passive"))
      (node (ref "C5") (pin "1") (pinfunction "1_1") (pintype "passive"))
      (node (ref "C6") (pin "1") (pinfunction "1_1") (pintype "passive"))
      (node (ref "C7") (pin "1") (pinfunction "1_1") (pintype "passive"))
      (node (ref "C8") (pin "1") (pinfunction "1_1") (pintype "passive"))
      (node (ref "C9") (pin "1") (pinfunction "1_1") (pintype "passive"))
      (node (ref "J1") (pin "8") (pinfunction "8_8") (pintype "passive"))
      (node (ref "J2") (pin "8") (pinfunction "8_8") (pintype "passive"))
      (node (ref "J3") (pin "0") (pinfunction "5_0") (pintype "passive"))
      (node (ref "J4") (pin "0") (pinfunction "5_0") (pintype "passive"))
      (node (ref "J5") (pin "8") (pinfunction "8_8") (pintype "passive"))
      (node (ref "J6") (pin "8") (pinfunction "8_8") (pintype "passive"))
      (node (ref "J7") (pin "0") (pinfunction "5_0") (pintype "passive"))
      (node (ref "J8") (pin "0") (pinfunction "5_0") (pintype "passive"))
      (node (ref "R1") (pin "1") (pinfunction "1_1") (pintype "passive"))
      (node (ref "R10") (pin "1") (pinfunction "1_1") (pintype "passive"))
      (node (ref "R15") (pin "2") (pinfunction "2_2") (pintype "passive"))
      (node (ref "R17") (pin "1") (pinfunction "1_1") (pintype "passive"))
      (node (ref "R18") (pin "2") (pinfunction "2_2") (pintype "passive"))
      (node (ref "R19") (pin "2") (pinfunction "2_2") (pintype "passive"))
      (node (ref "R23") (pin "2") (pinfunction "2_2") (pintype "passive"))
      (node (ref "R24") (pin "2") (pinfunction "2_2") (pintype "passive"))
      (node (ref "R25") (pin "2") (pinfunction "2_2") (pintype "passive"))
      (node (ref "R3") (pin "2") (pinfunction "2_2") (pintype "passive"))
      (node (ref "R4") (pin "2") (pinfunction "2_2") (pintype "passive"))
      (node (ref "R5") (pin "1") (pinfunction "1_1") (pintype "passive"))
      (node (ref "R8") (pin "2") (pinfunction "2_2") (pintype "passive"))
      (node (ref "TP14") (pin "0") (pinfunction "0_0") (pintype "passive"))
      (node (ref "TP15") (pin "0") (pinfunction "0_0") (pintype "passive"))
      (node (ref "TP16") (pin "0") (pinfunction "0_0") (pintype "passive"))
      (node (ref "TP17") (pin "0") (pinfunction "0_0") (pintype "passive"))
      (node (ref "TP20") (pin "0") (pinfunction "0_0") (pintype "passive"))
      (node (ref "TP21") (pin "0") (pinfunction "0_0") (pintype "passive"))
      (node (ref "TP23") (pin "0") (pinfunction "0_0") (pintype "passive"))
      (node (ref "U1") (pin "A2") (pinfunction "GND_A2") (pintype "passive"))
      (node (ref "U2") (pin "2") (pinfunction "V-_2") (pintype "passive"))
      (node (ref "U2") (pin "5") (pinfunction "1_5") (pintype "passive"))
      (node (ref "U3") (pin "2") (pinfunction "V-_2") (pintype "passive"))
      (node (ref "U3") (pin "5") (pinfunction "1_5") (pintype "passive"))
      (node (ref "U4") (pin "2") (pinfunction "V-_2") (pintype "passive"))
      (node (ref "U4") (pin "5") (pinfunction "1_5") (pintype "passive"))
      (node (ref "U5") (pin "0") (pinfunction "GND_0") (pintype "power_in"))
      (node (ref "U5") (pin "9") (pinfunction "GND_9") (pintype "power_in"))
    )
    (net (code "37") (name "Net-(LD1-LD)") (class "Default")
      (node (ref "LD1") (pin "1") (pinfunction "LD_1") (pintype "passive"))
      (node (ref "R12") (pin "2") (pinfunction "2_2") (pintype "passive"))
    )
    (net (code "38") (name "Net-(LED1-K)") (class "Default")
      (node (ref "LED1") (pin "1") (pinfunction "K_1") (pintype "passive"))
      (node (ref "R17") (pin "2") (pinfunction "2_2") (pintype "passive"))
    )
    (net (code "39") (name "Net-(Q1-D)") (class "Default")
      (node (ref "Q1") (pin "3") (pinfunction "D_3") (pintype "passive"))
      (node (ref "R12") (pin "1") (pinfunction "1_1") (pintype "passive"))
    )
    (net (code "40") (name "Net-(Q1-G)") (class "Default")
      (node (ref "Q1") (pin "1") (pinfunction "G_1") (pintype "passive"))
      (node (ref "R6") (pin "1") (pinfunction "1_1") (pintype "passive"))
      (node (ref "R7") (pin "1") (pinfunction "1_1") (pintype "passive"))
      (node (ref "TP15") (pin "1") (pinfunction "1_1") (pintype "passive"))
    )
    (net (code "41") (name "Net-(R6-Pad2)") (class "Default")
      (node (ref "R6") (pin "2") (pinfunction "2_2") (pintype "passive"))
      (node (ref "U2") (pin "1") (pinfunction "1_1") (pintype "passive"))
    )
    (net (code "42") (name "Net-(R11-Pad2)") (class "Default")
      (node (ref "R11") (pin "2") (pinfunction "2_2") (pintype "passive"))
      (node (ref "R13") (pin "1") (pinfunction "1_1") (pintype "passive"))
      (node (ref "U3") (pin "1") (pinfunction "1_1") (pintype "passive"))
    )
    (net (code "43") (name "Net-(U1-FB)") (class "Default")
      (node (ref "R1") (pin "2") (pinfunction "2_2") (pintype "passive"))
      (node (ref "R2") (pin "2") (pinfunction "2_2") (pintype "passive"))
      (node (ref "U1") (pin "B1") (pinfunction "FB_B1") (pintype "passive"))
    )
    (net (code "44") (name "Net-(U1-SW)") (class "Default")
      (node (ref "L1") (pin "1") (pinfunction "1_1") (pintype "passive"))
      (node (ref "U1") (pin "B2") (pinfunction "SW_B2") (pintype "passive"))
    )
    (net (code "45") (name "Net-(U1-VIN)") (class "Default")
      (node (ref "C8") (pin "2") (pinfunction "2_2") (pintype "passive"))
      (node (ref "C9") (pin "2") (pinfunction "2_2") (pintype "passive"))
      (node (ref "FB3") (pin "2") (pintype "passive"))
      (node (ref "L1") (pin "2") (pinfunction "2_2") (pintype "passive"))
      (node (ref "TP9") (pin "1") (pinfunction "1_1") (pintype "passive"))
      (node (ref "U1") (pin "A1") (pinfunction "VIN_A1") (pintype "passive"))
    )
    (net (code "46") (name "Net-(U1-VOUT)") (class "Default")
      (node (ref "C10") (pin "2") (pinfunction "2_2") (pintype "passive"))
      (node (ref "C11") (pin "2") (pinfunction "2_2") (pintype "passive"))
      (node (ref "FB4") (pin "1") (pintype "passive"))
      (node (ref "R2") (pin "1") (pinfunction "1_1") (pintype "passive"))
      (node (ref "TP12") (pin "1") (pinfunction "1_1") (pintype "passive"))
      (node (ref "U1") (pin "C2") (pinfunction "VOUT_C2") (pintype "passive"))
    )
    (net (code "47") (name "Net-(U2-V+)") (class "Default")
      (node (ref "C15") (pin "1") (pinfunction "1_1") (pintype "passive"))
      (node (ref "FB5") (pin "1") (pintype "passive"))
      (node (ref "U2") (pin "6") (pinfunction "V+_6") (pintype "passive"))
    )
    (net (code "48") (name "Net-(U3-+)") (class "Default")
      (node (ref "R8") (pin "1") (pinfunction "1_1") (pintype "passive"))
      (node (ref "R9") (pin "1") (pinfunction "1_1") (pintype "passive"))
      (node (ref "TP18") (pin "1") (pinfunction "1_1") (pintype "passive"))
      (node (ref "U3") (pin "3") (pinfunction "+_3") (pintype "passive"))
    )
    (net (code "49") (name "Net-(U3--)") (class "Default")
      (node (ref "C18") (pin "1") (pinfunction "1_1") (pintype "passive"))
      (node (ref "R13") (pin "2") (pinfunction "2_2") (pintype "passive"))
      (node (ref "U3") (pin "4") (pinfunction "-_4") (pintype "passive"))
    )
    (net (code "50") (name "Net-(U3-V+)") (class "Default")
      (node (ref "C17") (pin "1") (pinfunction "1_1") (pintype "passive"))
      (node (ref "FB6") (pin "2") (pintype "passive"))
      (node (ref "U3") (pin "6") (pinfunction "V+_6") (pintype "passive"))
    )
    (net (code "51") (name "Net-(U4-+)") (class "Default")
      (node (ref "R14") (pin "1") (pinfunction "1_1") (pintype "passive"))
      (node (ref "R15") (pin "1") (pinfunction "1_1") (pintype "passive"))
      (node (ref "TP19") (pin "1") (pinfunction "1_1") (pintype "passive"))
      (node (ref "U4") (pin "3") (pinfunction "+_3") (pintype "passive"))
    )
    (net (code "52") (name "Net-(U4-V+)") (class "Default")
      (node (ref "C19") (pin "1") (pinfunction "1_1") (pintype "passive"))
      (node (ref "FB7") (pin "1") (pintype "passive"))
      (node (ref "U4") (pin "6") (pinfunction "V+_6") (pintype "passive"))
    )
    (net (code "53") (name "Vd") (class "Default")
      (node (ref "C12") (pin "2") (pinfunction "2_2") (pintype "passive"))
      (node (ref "C13") (pin "2") (pinfunction "2_2") (pintype "passive"))
      (node (ref "FB4") (pin "2") (pintype "passive"))
      (node (ref "FB5") (pin "2") (pintype "passive"))
      (node (ref "LD1") (pin "2") (pinfunction "STEM_2") (pintype "passive"))
      (node (ref "LED1") (pin "2") (pinfunction "A_2") (pintype "passive"))
      (node (ref "PD1") (pin "1") (pinfunction "CA_1") (pintype "passive"))
      (node (ref "TP11") (pin "1") (pinfunction "1_1") (pintype "passive"))
    )
    (net (code "54") (name "Vs+") (class "Default")
      (node (ref "C21") (pin "1") (pinfunction "1_1") (pintype "passive"))
      (node (ref "C5") (pin "2") (pinfunction "2_2") (pintype "passive"))
      (node (ref "C7") (pin "2") (pinfunction "2_2") (pintype "passive"))
      (node (ref "FB2") (pin "1") (pintype "passive"))
      (node (ref "FB6") (pin "1") (pintype "passive"))
      (node (ref "FB7") (pin "2") (pintype "passive"))
      (node (ref "R14") (pin "2") (pinfunction "2_2") (pintype "passive"))
      (node (ref "R20") (pin "1") (pinfunction "1_1") (pintype "passive"))
      (node (ref "R21") (pin "1") (pinfunction "1_1") (pintype "passive"))
      (node (ref "R22") (pin "1") (pinfunction "1_1") (pintype "passive"))
      (node (ref "R9") (pin "2") (pinfunction "2_2") (pintype "passive"))
      (node (ref "SW1") (pin "1") (pinfunction "1_1") (pintype "passive"))
      (node (ref "SW1") (pin "2") (pinfunction "2_2") (pintype "passive"))
      (node (ref "TP10") (pin "1") (pinfunction "1_1") (pintype "passive"))
      (node (ref "U5") (pin "21") (pinfunction "VCC_21") (pintype "power_in"))
    )
    (net (code "55") (name "Vs-") (class "Default")
      (node (ref "C3") (pin "2") (pinfunction "2_2") (pintype "passive"))
      (node (ref "C4") (pin "2") (pinfunction "2_2") (pintype "passive"))
      (node (ref "FB1") (pin "1") (pintype "passive"))
      (node (ref "TP8") (pin "1") (pinfunction "1_1") (pintype "passive"))
    )
    (net (code "56") (name "unconnected-(M1-Pad1)") (class "Default")
      (node (ref "M1") (pin "1") (pinfunction "1_1") (pintype "passive+no_connect"))
    )
    (net (code "57") (name "unconnected-(M2-Pad1)") (class "Default")
      (node (ref "M2") (pin "1") (pinfunction "1_1") (pintype "passive+no_connect"))
    )
    (net (code "58") (name "unconnected-(M3-Pad1)") (class "Default")
      (node (ref "M3") (pin "1") (pinfunction "1_1") (pintype "passive+no_connect"))
    )
    (net (code "59") (name "unconnected-(M4-Pad1)") (class "Default")
      (node (ref "M4") (pin "1") (pinfunction "1_1") (pintype "passive+no_connect"))
    )
  )
)
